# 11_USB_schdoc.net
KiCad netlist of a schematic drawn in Altium Designer
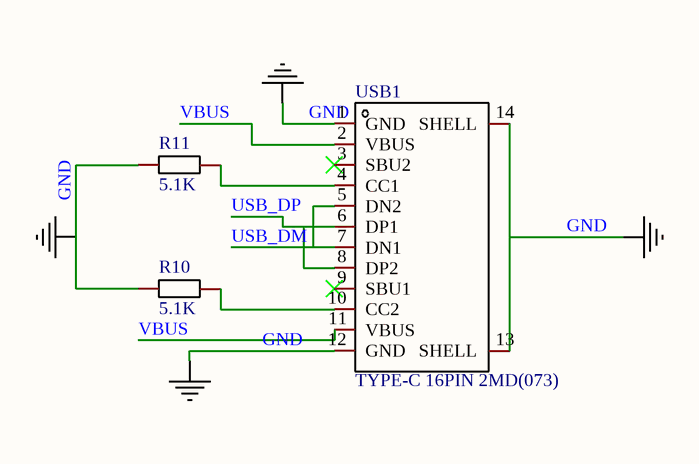
[diagram p0: 11_USB.schdoc.schdoc]

(export (version "E")
  (design (tool "Eeschema 10.0.6"))
  (components
    (comp (ref "R10")
      (value "5.1K")
      (fields (field (name "NAME") "5.1K"))
      (libsource (lib "altium-import") (part "root_0_Res_0603_"))
    )
    (comp (ref "R11")
      (value "5.1K")
      (fields (field (name "NAME") "5.1K"))
      (libsource (lib "altium-import") (part "root_0_Res_0603_"))
    )
    (comp (ref "USB1")
      (value "TYPE-C 16PIN 2MD(073)")
      (description "连接器类型:Type-C;标准:-;公母:母;触点数量:16P;端口数量:1;安装方式:卧贴;额定电流 - 电源:5A;工作温度范围:-25℃~+85℃;")
      (fields (field (name "NAME") "TYPE-C 16PIN 2MD(073)") (field (name "MANUFACTURER") "SHOU HAN(首韩)"))
      (libsource (lib "altium-import") (part "root_0_TYPE-C 16PIN 2MD(073)_"))
    )
  )
  (nets
    (net (code "1") (name "/GND") (class "Default")
      (node (ref "R10") (pin "1") (pinfunction "1_1") (pintype "passive"))
      (node (ref "R11") (pin "1") (pinfunction "1_1") (pintype "passive"))
      (node (ref "USB1") (pin "1") (pinfunction "GND_1") (pintype "passive"))
      (node (ref "USB1") (pin "12") (pinfunction "GND_12") (pintype "passive"))
      (node (ref "USB1") (pin "13") (pinfunction "SHELL_13") (pintype "passive"))
      (node (ref "USB1") (pin "14") (pinfunction "SHELL_14") (pintype "passive"))
    )
    (net (code "2") (name "/USB_DM") (class "Default")
      (node (ref "USB1") (pin "5") (pinfunction "DN2_5") (pintype "passive"))
      (node (ref "USB1") (pin "7") (pinfunction "DN1_7") (pintype "passive"))
    )
    (net (code "3") (name "/USB_DP") (class "Default")
      (node (ref "USB1") (pin "6") (pinfunction "DP1_6") (pintype "passive"))
      (node (ref "USB1") (pin "8") (pinfunction "DP2_8") (pintype "passive"))
    )
    (net (code "4") (name "/VBUS") (class "Default")
      (node (ref "USB1") (pin "11") (pinfunction "VBUS_11") (pintype "passive"))
      (node (ref "USB1") (pin "2") (pinfunction "VBUS_2") (pintype "passive"))
    )
    (net (code "5") (name "Net-(USB1-CC1)") (class "Default")
      (node (ref "R11") (pin "2") (pinfunction "2_2") (pintype "passive"))
      (node (ref "USB1") (pin "4") (pinfunction "CC1_4") (pintype "passive"))
    )
    (net (code "6") (name "Net-(USB1-CC2)") (class "Default")
      (node (ref "R10") (pin "2") (pinfunction "2_2") (pintype "passive"))
      (node (ref "USB1") (pin "10") (pinfunction "CC2_10") (pintype "passive"))
    )
    (net (code "7") (name "unconnected-(USB1-SBU1-Pad9)") (class "Default")
      (node (ref "USB1") (pin "9") (pinfunction "SBU1_9") (pintype "passive+no_connect"))
    )
    (net (code "8") (name "unconnected-(USB1-SBU2-Pad3)") (class "Default")
      (node (ref "USB1") (pin "3") (pinfunction "SBU2_3") (pintype "passive+no_connect"))
    )
  )
)
